# IR_Emitter_Card.net
KiCad netlist of a schematic drawn in EAGLE
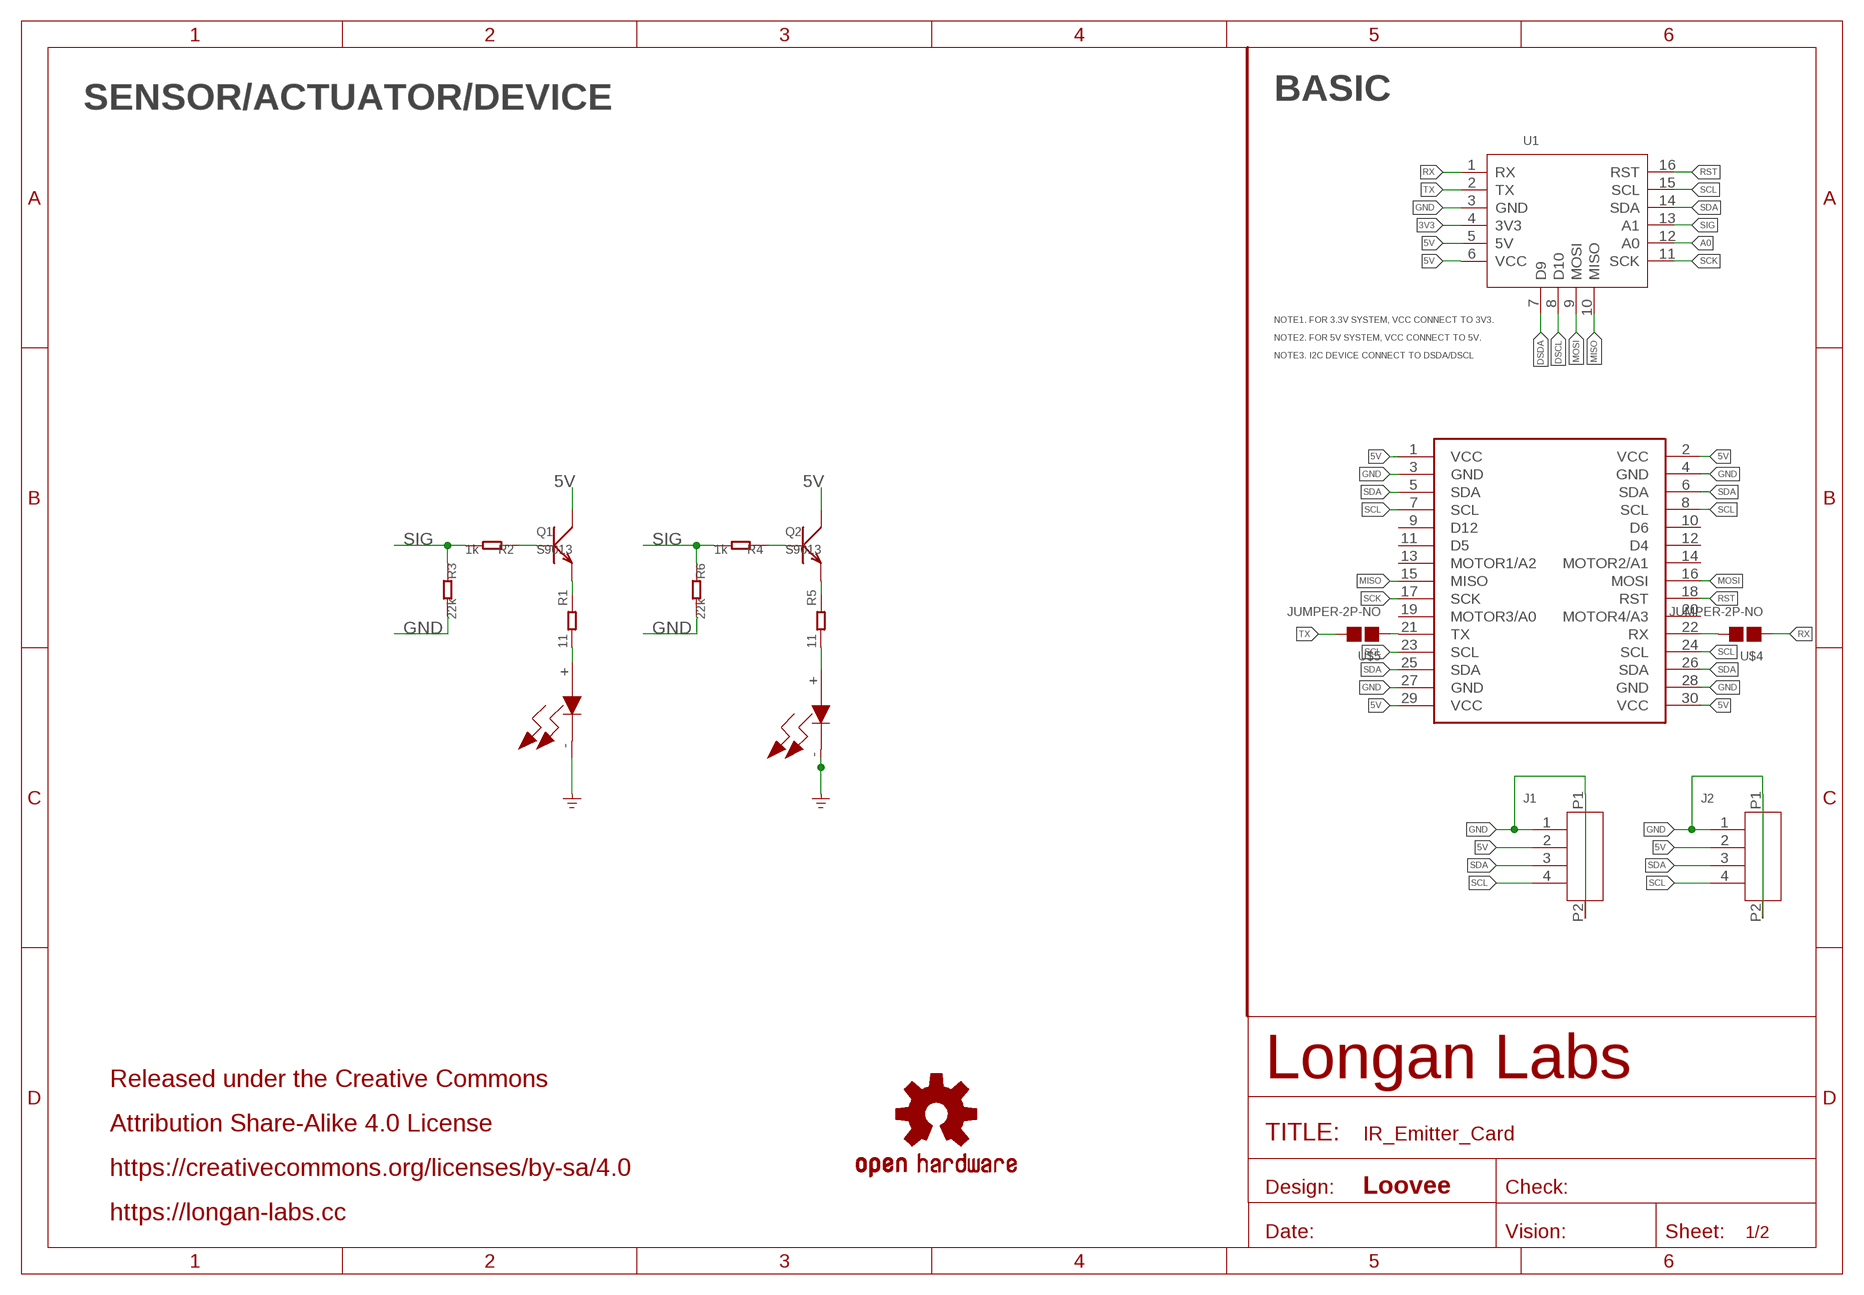
[diagram p0: schematic, sheet 1]

(export (version "E")
  (design (tool "Eeschema 10.0.6"))
  (components
    (comp (ref "J1")
      (value "HEADER-4P-1.0")
      (footprint "eagle-import:4P-1.0-90D")
      (libsource (lib "eagle-import") (part "HEADER-4P-1.0"))
    )
    (comp (ref "J2")
      (value "HEADER-4P-1.0")
      (footprint "eagle-import:4P-1.0-90D")
      (libsource (lib "eagle-import") (part "HEADER-4P-1.0"))
    )
    (comp (ref "LOGO2")
      (value "OSHW-LOGOS")
      (footprint "eagle-import:OSHW-LOGO-S")
      (libsource (lib "eagle-import") (part "OSHW-LOGOS"))
    )
    (comp (ref "MOUDLE1")
      (value "MOUDLE-2X15P-2.54'BOARD'")
      (footprint "eagle-import:MOUDLE-2X15P-2.54")
      (libsource (lib "eagle-import") (part "MOUDLE-2X15P-2.54'BOARD'"))
    )
    (comp (ref "Q1")
      (value "S9013")
      (footprint "eagle-import:SOT23")
      (libsource (lib "eagle-import") (part "TRANSISTOR-NPN-SOT23''"))
    )
    (comp (ref "Q2")
      (value "S9013")
      (footprint "eagle-import:SOT23")
      (libsource (lib "eagle-import") (part "TRANSISTOR-NPN-SOT23''"))
    )
    (comp (ref "R1")
      (value "11")
      (footprint "eagle-import:0805")
      (libsource (lib "eagle-import") (part "R-0805"))
    )
    (comp (ref "R2")
      (value "1k")
      (footprint "eagle-import:0603")
      (libsource (lib "eagle-import") (part "R-0603"))
    )
    (comp (ref "R3")
      (value "22k")
      (footprint "eagle-import:0603")
      (libsource (lib "eagle-import") (part "R-0603"))
    )
    (comp (ref "R4")
      (value "1k")
      (footprint "eagle-import:0603")
      (libsource (lib "eagle-import") (part "R-0603"))
    )
    (comp (ref "R5")
      (value "11")
      (footprint "eagle-import:0805")
      (libsource (lib "eagle-import") (part "R-0805"))
    )
    (comp (ref "R6")
      (value "22k")
      (footprint "eagle-import:0603")
      (libsource (lib "eagle-import") (part "R-0603"))
    )
    (comp (ref "U$4")
      (value "JUMPER-2P-NO")
      (footprint "eagle-import:2P-SMD-NO")
      (libsource (lib "eagle-import") (part "JUMPER-2P-NO"))
    )
    (comp (ref "U$5")
      (value "JUMPER-2P-NO")
      (footprint "eagle-import:2P-SMD-NO")
      (libsource (lib "eagle-import") (part "JUMPER-2P-NO"))
    )
    (comp (ref "U$8")
      (value "SENSOR-IR26")
      (footprint "eagle-import:2P-SMD-3.0X1.2MM")
      (libsource (lib "eagle-import") (part "SENSOR-IR26"))
    )
    (comp (ref "U$9")
      (value "SENSOR-IR26'90D'")
      (footprint "eagle-import:2P-SMD-3.0X1.2MM-90D")
      (libsource (lib "eagle-import") (part "SENSOR-IR26'90D'"))
    )
    (comp (ref "U1")
      (value "MOUDLE-CARDS")
      (footprint "eagle-import:16P-2.0-CARDS")
      (libsource (lib "eagle-import") (part "MOUDLE-CARDS"))
    )
  )
  (nets
    (net (code "1") (name "3V3") (class "Default")
      (node (ref "U1") (pin "4") (pinfunction "3V3_4") (pintype "bidirectional"))
    )
    (net (code "2") (name "5V") (class "Default")
      (node (ref "J1") (pin "2") (pinfunction "2_2") (pintype "bidirectional"))
      (node (ref "J2") (pin "2") (pinfunction "2_2") (pintype "bidirectional"))
      (node (ref "MOUDLE1") (pin "1") (pinfunction "VCC_1") (pintype "bidirectional"))
      (node (ref "MOUDLE1") (pin "2") (pinfunction "VCC_2") (pintype "bidirectional"))
      (node (ref "MOUDLE1") (pin "29") (pinfunction "VCC_29") (pintype "bidirectional"))
      (node (ref "MOUDLE1") (pin "30") (pinfunction "VCC_30") (pintype "bidirectional"))
      (node (ref "Q1") (pin "3") (pinfunction "C_3") (pintype "passive"))
      (node (ref "Q2") (pin "3") (pinfunction "C_3") (pintype "passive"))
      (node (ref "U1") (pin "5") (pinfunction "5V_5") (pintype "bidirectional"))
      (node (ref "U1") (pin "6") (pinfunction "VCC_6") (pintype "bidirectional"))
    )
    (net (code "3") (name "A0") (class "Default")
      (node (ref "U1") (pin "12") (pinfunction "A0_12") (pintype "bidirectional"))
    )
    (net (code "4") (name "DSCL") (class "Default")
      (node (ref "U1") (pin "8") (pinfunction "D10_8") (pintype "bidirectional"))
    )
    (net (code "5") (name "DSDA") (class "Default")
      (node (ref "U1") (pin "7") (pinfunction "D9_7") (pintype "bidirectional"))
    )
    (net (code "6") (name "GND") (class "Default")
      (node (ref "J1") (pin "1") (pinfunction "1_1") (pintype "bidirectional"))
      (node (ref "J1") (pin "P1") (pinfunction "P1_P1") (pintype "bidirectional"))
      (node (ref "J1") (pin "P2") (pinfunction "P2_P2") (pintype "bidirectional"))
      (node (ref "J2") (pin "1") (pinfunction "1_1") (pintype "bidirectional"))
      (node (ref "J2") (pin "P1") (pinfunction "P1_P1") (pintype "bidirectional"))
      (node (ref "J2") (pin "P2") (pinfunction "P2_P2") (pintype "bidirectional"))
      (node (ref "MOUDLE1") (pin "27") (pinfunction "GND_27") (pintype "bidirectional"))
      (node (ref "MOUDLE1") (pin "28") (pinfunction "GND_28") (pintype "bidirectional"))
      (node (ref "MOUDLE1") (pin "3") (pinfunction "GND_3") (pintype "bidirectional"))
      (node (ref "MOUDLE1") (pin "4") (pinfunction "GND_4") (pintype "bidirectional"))
      (node (ref "R3") (pin "2") (pinfunction "2_2") (pintype "passive"))
      (node (ref "R6") (pin "2") (pinfunction "2_2") (pintype "passive"))
      (node (ref "U$8") (pin "-") (pinfunction "-_-") (pintype "bidirectional"))
      (node (ref "U$9") (pin "-") (pinfunction "-_-") (pintype "bidirectional"))
      (node (ref "U1") (pin "3") (pinfunction "GND_3") (pintype "bidirectional"))
    )
    (net (code "7") (name "MISO") (class "Default")
      (node (ref "MOUDLE1") (pin "15") (pinfunction "MISO_15") (pintype "bidirectional"))
      (node (ref "U1") (pin "10") (pinfunction "MISO_10") (pintype "bidirectional"))
    )
    (net (code "8") (name "MOSI") (class "Default")
      (node (ref "MOUDLE1") (pin "16") (pinfunction "MOSI_16") (pintype "bidirectional"))
      (node (ref "U1") (pin "9") (pinfunction "MOSI_9") (pintype "bidirectional"))
    )
    (net (code "9") (name "Net-(MOUDLE1-RX)") (class "Default")
      (node (ref "MOUDLE1") (pin "22") (pinfunction "RX_22") (pintype "bidirectional"))
      (node (ref "U$4") (pin "2") (pinfunction "2_2") (pintype "bidirectional"))
    )
    (net (code "10") (name "Net-(MOUDLE1-TX)") (class "Default")
      (node (ref "MOUDLE1") (pin "21") (pinfunction "TX_21") (pintype "bidirectional"))
      (node (ref "U$5") (pin "1") (pinfunction "1_1") (pintype "bidirectional"))
    )
    (net (code "11") (name "Net-(Q1-B)") (class "Default")
      (node (ref "Q1") (pin "1") (pinfunction "B_1") (pintype "passive"))
      (node (ref "R2") (pin "1") (pinfunction "1_1") (pintype "passive"))
    )
    (net (code "12") (name "Net-(Q1-E)") (class "Default")
      (node (ref "Q1") (pin "2") (pinfunction "E_2") (pintype "passive"))
      (node (ref "R1") (pin "1") (pinfunction "1_1") (pintype "passive"))
    )
    (net (code "13") (name "Net-(Q2-B)") (class "Default")
      (node (ref "Q2") (pin "1") (pinfunction "B_1") (pintype "passive"))
      (node (ref "R4") (pin "1") (pinfunction "1_1") (pintype "passive"))
    )
    (net (code "14") (name "Net-(Q2-E)") (class "Default")
      (node (ref "Q2") (pin "2") (pinfunction "E_2") (pintype "passive"))
      (node (ref "R5") (pin "1") (pinfunction "1_1") (pintype "passive"))
    )
    (net (code "15") (name "Net-(R1-Pad2)") (class "Default")
      (node (ref "R1") (pin "2") (pinfunction "2_2") (pintype "passive"))
      (node (ref "U$8") (pin "+") (pinfunction "+_+") (pintype "bidirectional"))
    )
    (net (code "16") (name "Net-(R5-Pad2)") (class "Default")
      (node (ref "R5") (pin "2") (pinfunction "2_2") (pintype "passive"))
      (node (ref "U$9") (pin "+") (pinfunction "+_+") (pintype "bidirectional"))
    )
    (net (code "17") (name "RST") (class "Default")
      (node (ref "MOUDLE1") (pin "18") (pinfunction "RST_18") (pintype "bidirectional"))
      (node (ref "U1") (pin "16") (pinfunction "RST_16") (pintype "bidirectional"))
    )
    (net (code "18") (name "RX") (class "Default")
      (node (ref "U$4") (pin "1") (pinfunction "1_1") (pintype "bidirectional"))
      (node (ref "U1") (pin "1") (pinfunction "RX_1") (pintype "bidirectional"))
    )
    (net (code "19") (name "SCK") (class "Default")
      (node (ref "MOUDLE1") (pin "17") (pinfunction "SCK_17") (pintype "bidirectional"))
      (node (ref "U1") (pin "11") (pinfunction "SCK_11") (pintype "bidirectional"))
    )
    (net (code "20") (name "SCL") (class "Default")
      (node (ref "J1") (pin "4") (pinfunction "4_4") (pintype "bidirectional"))
      (node (ref "J2") (pin "4") (pinfunction "4_4") (pintype "bidirectional"))
      (node (ref "MOUDLE1") (pin "23") (pinfunction "SCL_23") (pintype "bidirectional"))
      (node (ref "MOUDLE1") (pin "24") (pinfunction "SCL_24") (pintype "bidirectional"))
      (node (ref "MOUDLE1") (pin "7") (pinfunction "SCL_7") (pintype "bidirectional"))
      (node (ref "MOUDLE1") (pin "8") (pinfunction "SCL_8") (pintype "bidirectional"))
      (node (ref "U1") (pin "15") (pinfunction "SCL_15") (pintype "bidirectional"))
    )
    (net (code "21") (name "SDA") (class "Default")
      (node (ref "J1") (pin "3") (pinfunction "3_3") (pintype "bidirectional"))
      (node (ref "J2") (pin "3") (pinfunction "3_3") (pintype "bidirectional"))
      (node (ref "MOUDLE1") (pin "25") (pinfunction "SDA_25") (pintype "bidirectional"))
      (node (ref "MOUDLE1") (pin "26") (pinfunction "SDA_26") (pintype "bidirectional"))
      (node (ref "MOUDLE1") (pin "5") (pinfunction "SDA_5") (pintype "bidirectional"))
      (node (ref "MOUDLE1") (pin "6") (pinfunction "SDA_6") (pintype "bidirectional"))
      (node (ref "U1") (pin "14") (pinfunction "SDA_14") (pintype "bidirectional"))
    )
    (net (code "22") (name "SIG") (class "Default")
      (node (ref "R2") (pin "2") (pinfunction "2_2") (pintype "passive"))
      (node (ref "R3") (pin "1") (pinfunction "1_1") (pintype "passive"))
      (node (ref "R4") (pin "2") (pinfunction "2_2") (pintype "passive"))
      (node (ref "R6") (pin "1") (pinfunction "1_1") (pintype "passive"))
      (node (ref "U1") (pin "13") (pinfunction "A1_13") (pintype "bidirectional"))
    )
    (net (code "23") (name "TX") (class "Default")
      (node (ref "U$5") (pin "2") (pinfunction "2_2") (pintype "bidirectional"))
      (node (ref "U1") (pin "2") (pinfunction "TX_2") (pintype "bidirectional"))
    )
    (net (code "24") (name "unconnected-(MOUDLE1-D4-Pad12)") (class "Default")
      (node (ref "MOUDLE1") (pin "12") (pinfunction "D4_12") (pintype "bidirectional"))
    )
    (net (code "25") (name "unconnected-(MOUDLE1-D5-Pad11)") (class "Default")
      (node (ref "MOUDLE1") (pin "11") (pinfunction "D5_11") (pintype "bidirectional"))
    )
    (net (code "26") (name "unconnected-(MOUDLE1-D6-Pad10)") (class "Default")
      (node (ref "MOUDLE1") (pin "10") (pinfunction "D6_10") (pintype "bidirectional"))
    )
    (net (code "27") (name "unconnected-(MOUDLE1-D12-Pad9)") (class "Default")
      (node (ref "MOUDLE1") (pin "9") (pinfunction "D12_9") (pintype "bidirectional"))
    )
    (net (code "28") (name "unconnected-(MOUDLE1-MOTOR1{slash}A2-Pad13)") (class "Default")
      (node (ref "MOUDLE1") (pin "13") (pinfunction "MOTOR1/A2_13") (pintype "bidirectional"))
    )
    (net (code "29") (name "unconnected-(MOUDLE1-MOTOR2{slash}A1-Pad14)") (class "Default")
      (node (ref "MOUDLE1") (pin "14") (pinfunction "MOTOR2/A1_14") (pintype "bidirectional"))
    )
    (net (code "30") (name "unconnected-(MOUDLE1-MOTOR3{slash}A0-Pad19)") (class "Default")
      (node (ref "MOUDLE1") (pin "19") (pinfunction "MOTOR3/A0_19") (pintype "bidirectional"))
    )
    (net (code "31") (name "unconnected-(MOUDLE1-MOTOR4{slash}A3-Pad20)") (class "Default")
      (node (ref "MOUDLE1") (pin "20") (pinfunction "MOTOR4/A3_20") (pintype "bidirectional"))
    )
  )
)
